# GR_Propulsion.net
KiCad netlist of a schematic drawn in Altium Designer
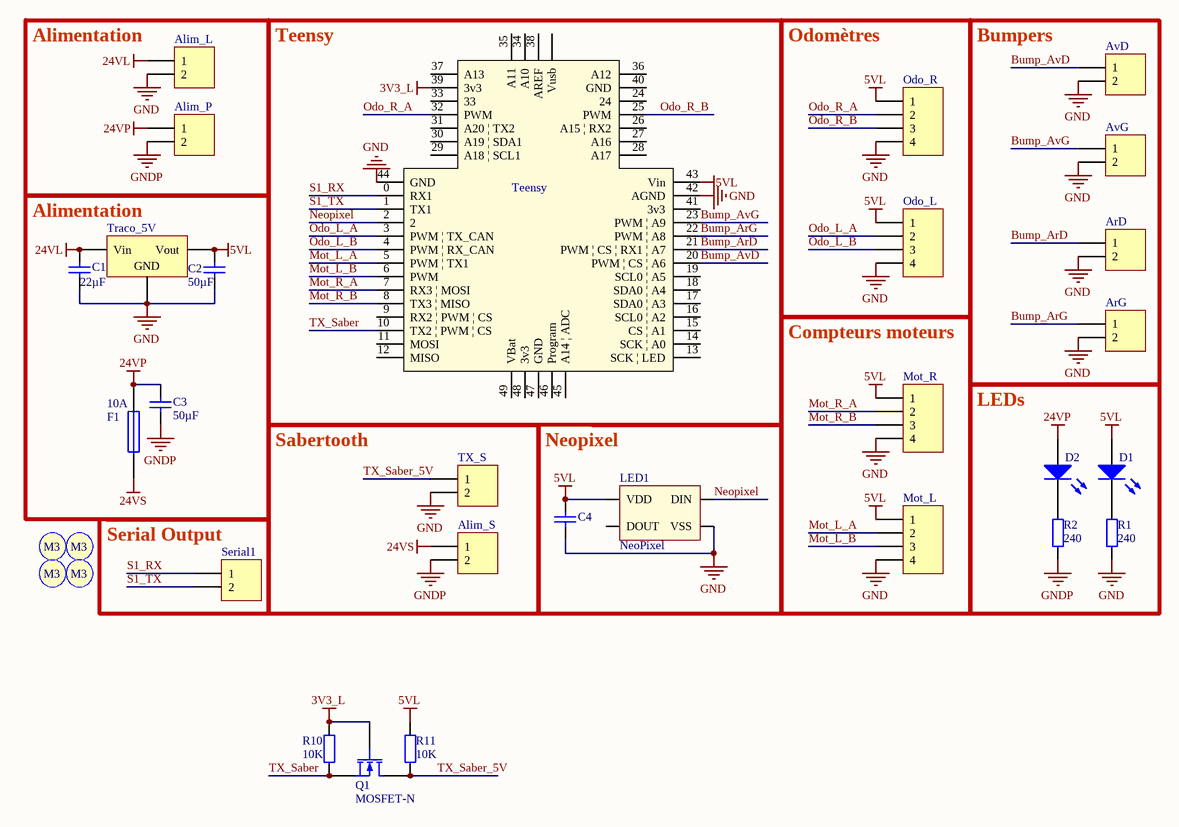
[diagram p0: GR_Propulsion.SchDoc]

(export (version "E")
  (design (tool "Eeschema 10.0.6"))
  (components
    (comp (ref "Alim_L")
      (value "Minifit Jr 2x1H")
      (footprint "Robot_2019:Molex_MiniFitJr_2x1H")
      (description "Molex Minifit Jr 2x1H")
      (fields (field (name "PUBLISHER") "Altium Limited"))
      (libsource (lib "Miscellaneous Connectors") (part "Header 2"))
    )
    (comp (ref "Alim_P")
      (value "Minifit Jr 2x1H")
      (footprint "Robot_2019:Molex_MiniFitJr_2x1H")
      (description "Molex Minifit Jr 2x1H")
      (fields (field (name "PUBLISHER") "Altium Limited"))
      (libsource (lib "Miscellaneous Connectors") (part "Header 2"))
    )
    (comp (ref "Alim_S")
      (value "Minifit Jr 2x1H")
      (footprint "Robot_2019:Molex_MiniFitJr_2x1H")
      (description "Molex Minifit Jr 2x1H")
      (fields (field (name "PUBLISHER") "Altium Limited"))
      (libsource (lib "Miscellaneous Connectors") (part "Header 2"))
    )
    (comp (ref "ArD")
      (value "SPOX 2x1H")
      (footprint "Robot_2019:Molex SPOX 2x1H")
      (description "Molex SPOX Jr 2x1H")
      (fields (field (name "PUBLISHER") "Altium Limited"))
      (libsource (lib "Miscellaneous Connectors") (part "Header 2"))
    )
    (comp (ref "ArG")
      (value "SPOX 2x1H")
      (footprint "Robot_2019:Molex SPOX 2x1H")
      (description "Molex SPOX Jr 2x1H")
      (fields (field (name "PUBLISHER") "Altium Limited"))
      (libsource (lib "Miscellaneous Connectors") (part "Header 2"))
    )
    (comp (ref "AvD")
      (value "SPOX 2x1H")
      (footprint "Robot_2019:Molex SPOX 2x1H")
      (description "Molex SPOX Jr 2x1H")
      (fields (field (name "PUBLISHER") "Altium Limited"))
      (libsource (lib "Miscellaneous Connectors") (part "Header 2"))
    )
    (comp (ref "AvG")
      (value "SPOX 2x1H")
      (footprint "Robot_2019:Molex SPOX 2x1H")
      (description "Molex SPOX Jr 2x1H")
      (fields (field (name "PUBLISHER") "Altium Limited"))
      (libsource (lib "Miscellaneous Connectors") (part "Header 2"))
    )
    (comp (ref "C1")
      (value "22µF")
      (footprint "3.2X1.6X1.1")
      (description "Capacitor")
      (fields (field (name "Comment") "Cap22uF") (field (name "PUBLISHER") "Altium Limited"))
      (libsource (lib "Miscellaneous Devices") (part "Cap"))
    )
    (comp (ref "C2")
      (value "50µF")
      (footprint "3.2X1.6X1.1")
      (description "Capacitor")
      (fields (field (name "Comment") "Cap50uF") (field (name "PUBLISHER") "Altium Limited"))
      (libsource (lib "Miscellaneous Devices") (part "Cap"))
    )
    (comp (ref "C3")
      (value "50µF")
      (footprint "Robot_2019:Condensateur")
      (description "Capacitor")
      (fields (field (name "Comment") "Cap50uF") (field (name "PUBLISHER") "Altium Limited"))
      (libsource (lib "Miscellaneous Devices") (part "Cap"))
    )
    (comp (ref "C4")
      (value "Cap")
      (footprint "3.2X1.6X1.1")
      (description "Capacitor")
      (fields (field (name "PUBLISHER") "Altium Limited"))
      (libsource (lib "Miscellaneous Devices") (part "Cap"))
    )
    (comp (ref "D1")
      (value "LED1")
      (footprint "3.2X1.6X1.1")
      (description "Typical RED, GREEN, YELLOW, AMBER GaAs LED")
      (fields (field (name "PUBLISHER") "Altium Limited"))
      (libsource (lib "Miscellaneous Devices") (part "LED2"))
    )
    (comp (ref "D2")
      (value "LED2")
      (footprint "3.2X1.6X1.1")
      (description "Typical RED, GREEN, YELLOW, AMBER GaAs LED")
      (fields (field (name "PUBLISHER") "Altium Limited"))
      (libsource (lib "Miscellaneous Devices") (part "LED2"))
    )
    (comp (ref "F1")
      (value "10A")
      (footprint "Robot_2019:Fuse")
      (description "Fuse")
      (fields (field (name "PUBLISHER") "Altium Limited"))
      (libsource (lib "Miscellaneous Devices") (part "Fuse 1"))
    )
    (comp (ref "LED1")
      (value "NeoPixel")
      (footprint "Robot_2019:Neopixel")
      (libsource (lib "Robot_2019") (part "NeoPixel"))
    )
    (comp (ref "Mot_L")
      (value "SPOX 4x1H")
      (footprint "Robot_2019:Molex SPOX 4x1H")
      (description "Molex SPOX 4x1H")
      (fields (field (name "PUBLISHER") "Altium Limited"))
      (libsource (lib "Miscellaneous Connectors") (part "Header 4H"))
    )
    (comp (ref "Mot_R")
      (value "SPOX 4x1H")
      (footprint "Robot_2019:Molex SPOX 4x1H")
      (description "Molex SPOX 4x1H")
      (fields (field (name "PUBLISHER") "Altium Limited"))
      (libsource (lib "Miscellaneous Connectors") (part "Header 4H"))
    )
    (comp (ref "Odo_L")
      (value "SPOX 4x1H")
      (footprint "Robot_2019:Molex SPOX 4x1H")
      (description "Molex SPOX 4x1H")
      (fields (field (name "PUBLISHER") "Altium Limited"))
      (libsource (lib "Miscellaneous Connectors") (part "Header 4H"))
    )
    (comp (ref "Odo_R")
      (value "SPOX 4x1H")
      (footprint "Robot_2019:Molex SPOX 4x1H")
      (description "Molex SPOX 4x1H")
      (fields (field (name "PUBLISHER") "Altium Limited"))
      (libsource (lib "Miscellaneous Connectors") (part "Header 4H"))
    )
    (comp (ref "Q1")
      (value "MOSFET-N")
      (footprint "SOT23_N")
      (description "N-Channel MOSFET")
      (fields (field (name "PUBLISHER") "Altium Limited"))
      (libsource (lib "Miscellaneous Devices") (part "MOSFET-N"))
    )
    (comp (ref "R1")
      (value "240")
      (footprint "3.2X1.6X1.1")
      (description "Resistor")
      (fields (field (name "Comment") "Res2") (field (name "PUBLISHER") "Altium Limited"))
      (libsource (lib "Miscellaneous Devices") (part "Res2"))
    )
    (comp (ref "R2")
      (value "240")
      (footprint "3.2X1.6X1.1")
      (description "Resistor")
      (fields (field (name "Comment") "Res2") (field (name "PUBLISHER") "Altium Limited"))
      (libsource (lib "Miscellaneous Devices") (part "Res2"))
    )
    (comp (ref "R10")
      (value "10K")
      (footprint "3.2X1.6X1.1")
      (description "Resistor")
      (fields (field (name "Comment") "Res2") (field (name "PUBLISHER") "Altium Limited"))
      (libsource (lib "Miscellaneous Devices") (part "Res2"))
    )
    (comp (ref "R11")
      (value "10K")
      (footprint "3.2X1.6X1.1")
      (description "Resistor")
      (fields (field (name "Comment") "Res2") (field (name "PUBLISHER") "Altium Limited"))
      (libsource (lib "Miscellaneous Devices") (part "Res2"))
    )
    (comp (ref "S1")
      (value "Screw M3")
      (footprint "Robot_2019:Screw M3")
      (libsource (lib "Robot_2019") (part "Screw M3"))
    )
    (comp (ref "S2")
      (value "Screw M3")
      (footprint "Robot_2019:Screw M3")
      (libsource (lib "Robot_2019") (part "Screw M3"))
    )
    (comp (ref "S3")
      (value "Screw M3")
      (footprint "Robot_2019:Screw M3")
      (libsource (lib "Robot_2019") (part "Screw M3"))
    )
    (comp (ref "S4")
      (value "Screw M3")
      (footprint "Robot_2019:Screw M3")
      (libsource (lib "Robot_2019") (part "Screw M3"))
    )
    (comp (ref "Serial1")
      (value "SPOX 2x1H")
      (footprint "Robot_2019:Molex SPOX 2x1H")
      (description "Molex SPOX Jr 2x1H")
      (fields (field (name "PUBLISHER") "Altium Limited"))
      (libsource (lib "Miscellaneous Connectors") (part "Header 2"))
    )
    (comp (ref "Teensy")
      (value "Teensy 3.2")
      (footprint "Robot_2019:teensy")
      (libsource (lib "Robot_2019") (part "teensy3.2"))
    )
    (comp (ref "Traco_5V")
      (value "Traco TRS2-2450")
      (footprint "Robot_2019:TRS")
      (description "Voltage Regulator")
      (fields (field (name "PUBLISHER") "Altium Limited"))
      (libsource (lib "Miscellaneous Devices") (part "Volt Reg"))
    )
    (comp (ref "TX_S")
      (value "SPOX 2x1H")
      (footprint "Robot_2019:Molex SPOX 2x1H")
      (description "Molex SPOX Jr 2x1H")
      (fields (field (name "PUBLISHER") "Altium Limited"))
      (libsource (lib "Miscellaneous Connectors") (part "Header 2"))
    )
  )
  (nets
    (net (code "1") (name "/Bump_ArD") (class "Default")
      (node (ref "ArD") (pin "1") (pinfunction "1_1") (pintype "passive"))
      (node (ref "Teensy") (pin "21") (pinfunction "PWM_¦_CS_¦_RX1_¦_A7_21") (pintype "passive"))
    )
    (net (code "2") (name "/Bump_ArG") (class "Default")
      (node (ref "ArG") (pin "1") (pinfunction "1_1") (pintype "passive"))
      (node (ref "Teensy") (pin "22") (pinfunction "PWM_¦_A8_22") (pintype "passive"))
    )
    (net (code "3") (name "/Bump_AvD") (class "Default")
      (node (ref "AvD") (pin "1") (pinfunction "1_1") (pintype "passive"))
      (node (ref "Teensy") (pin "20") (pinfunction "PWM_¦_CS_¦_A6_20") (pintype "passive"))
    )
    (net (code "4") (name "/Bump_AvG") (class "Default")
      (node (ref "AvG") (pin "1") (pinfunction "1_1") (pintype "passive"))
      (node (ref "Teensy") (pin "23") (pinfunction "PWM_¦_A9_23") (pintype "passive"))
    )
    (net (code "5") (name "/Mot_L_A") (class "Default")
      (node (ref "Mot_L") (pin "2") (pinfunction "2_2") (pintype "passive"))
      (node (ref "Teensy") (pin "5") (pinfunction "PWM_¦_TX1_5") (pintype "passive"))
    )
    (net (code "6") (name "/Mot_L_B") (class "Default")
      (node (ref "Mot_L") (pin "3") (pinfunction "3_3") (pintype "passive"))
      (node (ref "Teensy") (pin "6") (pinfunction "PWM_6") (pintype "passive"))
    )
    (net (code "7") (name "/Mot_R_A") (class "Default")
      (node (ref "Mot_R") (pin "2") (pinfunction "2_2") (pintype "passive"))
      (node (ref "Teensy") (pin "7") (pinfunction "RX3_¦_MOSI_7") (pintype "passive"))
    )
    (net (code "8") (name "/Mot_R_B") (class "Default")
      (node (ref "Mot_R") (pin "3") (pinfunction "3_3") (pintype "passive"))
      (node (ref "Teensy") (pin "8") (pinfunction "TX3_¦_MISO_8") (pintype "passive"))
    )
    (net (code "9") (name "/Neopixel") (class "Default")
      (node (ref "LED1") (pin "2") (pinfunction "DIN_2") (pintype "passive"))
      (node (ref "Teensy") (pin "2") (pinfunction "2_2") (pintype "passive"))
    )
    (net (code "10") (name "/Odo_L_A") (class "Default")
      (node (ref "Odo_L") (pin "2") (pinfunction "2_2") (pintype "passive"))
      (node (ref "Teensy") (pin "3") (pinfunction "PWM_¦_TX_CAN_3") (pintype "passive"))
    )
    (net (code "11") (name "/Odo_L_B") (class "Default")
      (node (ref "Odo_L") (pin "3") (pinfunction "3_3") (pintype "passive"))
      (node (ref "Teensy") (pin "4") (pinfunction "PWM_¦_RX_CAN_4") (pintype "passive"))
    )
    (net (code "12") (name "/Odo_R_A") (class "Default")
      (node (ref "Odo_R") (pin "2") (pinfunction "2_2") (pintype "passive"))
      (node (ref "Teensy") (pin "32") (pinfunction "PWM_32") (pintype "passive"))
    )
    (net (code "13") (name "/Odo_R_B") (class "Default")
      (node (ref "Odo_R") (pin "3") (pinfunction "3_3") (pintype "passive"))
      (node (ref "Teensy") (pin "25") (pinfunction "PWM_25") (pintype "passive"))
    )
    (net (code "14") (name "/S1_RX") (class "Default")
      (node (ref "Serial1") (pin "1") (pinfunction "1_1") (pintype "passive"))
      (node (ref "Teensy") (pin "0") (pinfunction "RX1_0") (pintype "passive"))
    )
    (net (code "15") (name "/S1_TX") (class "Default")
      (node (ref "Serial1") (pin "2") (pinfunction "2_2") (pintype "passive"))
      (node (ref "Teensy") (pin "1") (pinfunction "TX1_1") (pintype "passive"))
    )
    (net (code "16") (name "/TX_Saber") (class "Default")
      (node (ref "Q1") (pin "3") (pinfunction "S_3") (pintype "passive"))
      (node (ref "R10") (pin "2") (pinfunction "2_2") (pintype "passive"))
      (node (ref "Teensy") (pin "10") (pinfunction "TX2_¦_PWM_¦_CS_10") (pintype "passive"))
    )
    (net (code "17") (name "/TX_Saber_5V") (class "Default")
      (node (ref "Q1") (pin "1") (pinfunction "D_1") (pintype "passive"))
      (node (ref "R11") (pin "2") (pinfunction "2_2") (pintype "passive"))
      (node (ref "TX_S") (pin "1") (pinfunction "1_1") (pintype "passive"))
    )
    (net (code "18") (name "3V3_L") (class "Default")
      (node (ref "Q1") (pin "2") (pinfunction "G_2") (pintype "passive"))
      (node (ref "R10") (pin "1") (pinfunction "1_1") (pintype "passive"))
      (node (ref "Teensy") (pin "39") (pinfunction "3v3_39") (pintype "passive"))
    )
    (net (code "19") (name "5VL") (class "Default")
      (node (ref "C2") (pin "1") (pinfunction "1_1") (pintype "passive"))
      (node (ref "C4") (pin "2") (pinfunction "2_2") (pintype "passive"))
      (node (ref "D1") (pin "1") (pinfunction "A_1") (pintype "passive"))
      (node (ref "LED1") (pin "3") (pinfunction "VDD_3") (pintype "passive"))
      (node (ref "Mot_L") (pin "1") (pinfunction "1_1") (pintype "passive"))
      (node (ref "Mot_R") (pin "1") (pinfunction "1_1") (pintype "passive"))
      (node (ref "Odo_L") (pin "1") (pinfunction "1_1") (pintype "passive"))
      (node (ref "Odo_R") (pin "1") (pinfunction "1_1") (pintype "passive"))
      (node (ref "R11") (pin "1") (pinfunction "1_1") (pintype "passive"))
      (node (ref "Teensy") (pin "43") (pinfunction "Vin_43") (pintype "passive"))
      (node (ref "Traco_5V") (pin "3") (pinfunction "Vout_3") (pintype "passive"))
    )
    (net (code "20") (name "24VL") (class "Default")
      (node (ref "Alim_L") (pin "1") (pinfunction "1_1") (pintype "passive"))
      (node (ref "C1") (pin "2") (pinfunction "2_2") (pintype "passive"))
      (node (ref "Traco_5V") (pin "1") (pinfunction "Vin_1") (pintype "passive"))
    )
    (net (code "21") (name "24VP") (class "Default")
      (node (ref "Alim_P") (pin "1") (pinfunction "1_1") (pintype "passive"))
      (node (ref "C3") (pin "1") (pinfunction "1_1") (pintype "passive"))
      (node (ref "D2") (pin "1") (pinfunction "A_1") (pintype "passive"))
      (node (ref "F1") (pin "2") (pinfunction "2_2") (pintype "passive"))
    )
    (net (code "22") (name "24VS") (class "Default")
      (node (ref "Alim_S") (pin "1") (pinfunction "1_1") (pintype "passive"))
      (node (ref "F1") (pin "1") (pinfunction "1_1") (pintype "passive"))
    )
    (net (code "23") (name "GND") (class "Default")
      (node (ref "Alim_L") (pin "2") (pinfunction "2_2") (pintype "passive"))
      (node (ref "ArD") (pin "2") (pinfunction "2_2") (pintype "passive"))
      (node (ref "ArG") (pin "2") (pinfunction "2_2") (pintype "passive"))
      (node (ref "AvD") (pin "2") (pinfunction "2_2") (pintype "passive"))
      (node (ref "AvG") (pin "2") (pinfunction "2_2") (pintype "passive"))
      (node (ref "C1") (pin "1") (pinfunction "1_1") (pintype "passive"))
      (node (ref "C2") (pin "2") (pinfunction "2_2") (pintype "passive"))
      (node (ref "C4") (pin "1") (pinfunction "1_1") (pintype "passive"))
      (node (ref "LED1") (pin "1") (pinfunction "VSS_1") (pintype "passive"))
      (node (ref "Mot_L") (pin "4") (pinfunction "4_4") (pintype "passive"))
      (node (ref "Mot_R") (pin "4") (pinfunction "4_4") (pintype "passive"))
      (node (ref "Odo_L") (pin "4") (pinfunction "4_4") (pintype "passive"))
      (node (ref "Odo_R") (pin "4") (pinfunction "4_4") (pintype "passive"))
      (node (ref "R1") (pin "2") (pinfunction "2_2") (pintype "passive"))
      (node (ref "TX_S") (pin "2") (pinfunction "2_2") (pintype "passive"))
      (node (ref "Teensy") (pin "42") (pinfunction "AGND_42") (pintype "passive"))
      (node (ref "Teensy") (pin "44") (pinfunction "GND_44") (pintype "passive"))
      (node (ref "Traco_5V") (pin "2") (pinfunction "GND_2") (pintype "passive"))
    )
    (net (code "24") (name "GNDP") (class "Default")
      (node (ref "Alim_P") (pin "2") (pinfunction "2_2") (pintype "passive"))
      (node (ref "Alim_S") (pin "2") (pinfunction "2_2") (pintype "passive"))
      (node (ref "C3") (pin "2") (pinfunction "2_2") (pintype "passive"))
      (node (ref "R2") (pin "2") (pinfunction "2_2") (pintype "passive"))
    )
    (net (code "25") (name "Net-(D1-K)") (class "Default")
      (node (ref "D1") (pin "2") (pinfunction "K_2") (pintype "passive"))
      (node (ref "R1") (pin "1") (pinfunction "1_1") (pintype "passive"))
    )
    (net (code "26") (name "Net-(D2-K)") (class "Default")
      (node (ref "D2") (pin "2") (pinfunction "K_2") (pintype "passive"))
      (node (ref "R2") (pin "1") (pinfunction "1_1") (pintype "passive"))
    )
    (net (code "27") (name "unconnected-(LED1-DOUT-Pad4)") (class "Default")
      (node (ref "LED1") (pin "4") (pinfunction "DOUT_4") (pintype "passive"))
    )
    (net (code "28") (name "unconnected-(Teensy-3v3-Pad41)") (class "Default")
      (node (ref "Teensy") (pin "41") (pinfunction "3v3_41") (pintype "passive"))
    )
    (net (code "29") (name "unconnected-(Teensy-3v3-Pad48)") (class "Default")
      (node (ref "Teensy") (pin "48") (pinfunction "3v3_48") (pintype "passive"))
    )
    (net (code "30") (name "unconnected-(Teensy-A10-Pad34)") (class "Default")
      (node (ref "Teensy") (pin "34") (pinfunction "A10_34") (pintype "passive"))
    )
    (net (code "31") (name "unconnected-(Teensy-A11-Pad35)") (class "Default")
      (node (ref "Teensy") (pin "35") (pinfunction "A11_35") (pintype "passive"))
    )
    (net (code "32") (name "unconnected-(Teensy-A12-Pad36)") (class "Default")
      (node (ref "Teensy") (pin "36") (pinfunction "A12_36") (pintype "passive"))
    )
    (net (code "33") (name "unconnected-(Teensy-A13-Pad37)") (class "Default")
      (node (ref "Teensy") (pin "37") (pinfunction "A13_37") (pintype "passive"))
    )
    (net (code "34") (name "unconnected-(Teensy-A14_¦_ADC-Pad45)") (class "Default")
      (node (ref "Teensy") (pin "45") (pinfunction "A14_¦_ADC_45") (pintype "passive"))
    )
    (net (code "35") (name "unconnected-(Teensy-A15_¦_RX2-Pad26)") (class "Default")
      (node (ref "Teensy") (pin "26") (pinfunction "A15_¦_RX2_26") (pintype "passive"))
    )
    (net (code "36") (name "unconnected-(Teensy-A16-Pad27)") (class "Default")
      (node (ref "Teensy") (pin "27") (pinfunction "A16_27") (pintype "passive"))
    )
    (net (code "37") (name "unconnected-(Teensy-A17-Pad28)") (class "Default")
      (node (ref "Teensy") (pin "28") (pinfunction "A17_28") (pintype "passive"))
    )
    (net (code "38") (name "unconnected-(Teensy-A18_¦_SCL1-Pad29)") (class "Default")
      (node (ref "Teensy") (pin "29") (pinfunction "A18_¦_SCL1_29") (pintype "passive"))
    )
    (net (code "39") (name "unconnected-(Teensy-A19_¦_SDA1-Pad30)") (class "Default")
      (node (ref "Teensy") (pin "30") (pinfunction "A19_¦_SDA1_30") (pintype "passive"))
    )
    (net (code "40") (name "unconnected-(Teensy-A20_¦_TX2-Pad31)") (class "Default")
      (node (ref "Teensy") (pin "31") (pinfunction "A20_¦_TX2_31") (pintype "passive"))
    )
    (net (code "41") (name "unconnected-(Teensy-AREF-Pad38)") (class "Default")
      (node (ref "Teensy") (pin "38") (pinfunction "AREF_38") (pintype "passive"))
    )
    (net (code "42") (name "unconnected-(Teensy-CS_¦_A1-Pad15)") (class "Default")
      (node (ref "Teensy") (pin "15") (pinfunction "CS_¦_A1_15") (pintype "passive"))
    )
    (net (code "43") (name "unconnected-(Teensy-GND-Pad40)") (class "Default")
      (node (ref "Teensy") (pin "40") (pinfunction "GND_40") (pintype "passive"))
    )
    (net (code "44") (name "unconnected-(Teensy-GND-Pad47)") (class "Default")
      (node (ref "Teensy") (pin "47") (pinfunction "GND_47") (pintype "passive"))
    )
    (net (code "45") (name "unconnected-(Teensy-MISO-Pad12)") (class "Default")
      (node (ref "Teensy") (pin "12") (pinfunction "MISO_12") (pintype "passive"))
    )
    (net (code "46") (name "unconnected-(Teensy-MOSI-Pad11)") (class "Default")
      (node (ref "Teensy") (pin "11") (pinfunction "MOSI_11") (pintype "passive"))
    )
    (net (code "47") (name "unconnected-(Teensy-Pad24)") (class "Default")
      (node (ref "Teensy") (pin "24") (pinfunction "24_24") (pintype "passive"))
    )
    (net (code "48") (name "unconnected-(Teensy-Pad33)") (class "Default")
      (node (ref "Teensy") (pin "33") (pinfunction "33_33") (pintype "passive"))
    )
    (net (code "49") (name "unconnected-(Teensy-Program-Pad46)") (class "Default")
      (node (ref "Teensy") (pin "46") (pinfunction "Program_46") (pintype "passive"))
    )
    (net (code "50") (name "unconnected-(Teensy-RX2_¦_PWM_¦_CS-Pad9)") (class "Default")
      (node (ref "Teensy") (pin "9") (pinfunction "RX2_¦_PWM_¦_CS_9") (pintype "passive"))
    )
    (net (code "51") (name "unconnected-(Teensy-SCK_¦_A0-Pad14)") (class "Default")
      (node (ref "Teensy") (pin "14") (pinfunction "SCK_¦_A0_14") (pintype "passive"))
    )
    (net (code "52") (name "unconnected-(Teensy-SCK_¦_LED-Pad13)") (class "Default")
      (node (ref "Teensy") (pin "13") (pinfunction "SCK_¦_LED_13") (pintype "passive"))
    )
    (net (code "53") (name "unconnected-(Teensy-SCL0_¦_A2-Pad16)") (class "Default")
      (node (ref "Teensy") (pin "16") (pinfunction "SCL0_¦_A2_16") (pintype "passive"))
    )
    (net (code "54") (name "unconnected-(Teensy-SCL0_¦_A5-Pad19)") (class "Default")
      (node (ref "Teensy") (pin "19") (pinfunction "SCL0_¦_A5_19") (pintype "passive"))
    )
    (net (code "55") (name "unconnected-(Teensy-SDA0_¦_A3-Pad17)") (class "Default")
      (node (ref "Teensy") (pin "17") (pinfunction "SDA0_¦_A3_17") (pintype "passive"))
    )
    (net (code "56") (name "unconnected-(Teensy-SDA0_¦_A4-Pad18)") (class "Default")
      (node (ref "Teensy") (pin "18") (pinfunction "SDA0_¦_A4_18") (pintype "passive"))
    )
    (net (code "57") (name "unconnected-(Teensy-VBat-Pad49)") (class "Default")
      (node (ref "Teensy") (pin "49") (pinfunction "VBat_49") (pintype "passive"))
    )
    (net (code "58") (name "unconnected-(Teensy-Vusb-Pad50)") (class "Default")
      (node (ref "Teensy") (pin "50") (pinfunction "Vusb_50") (pintype "passive"))
    )
  )
)
